# mowgli.net
KiCad netlist of a schematic drawn in EAGLE
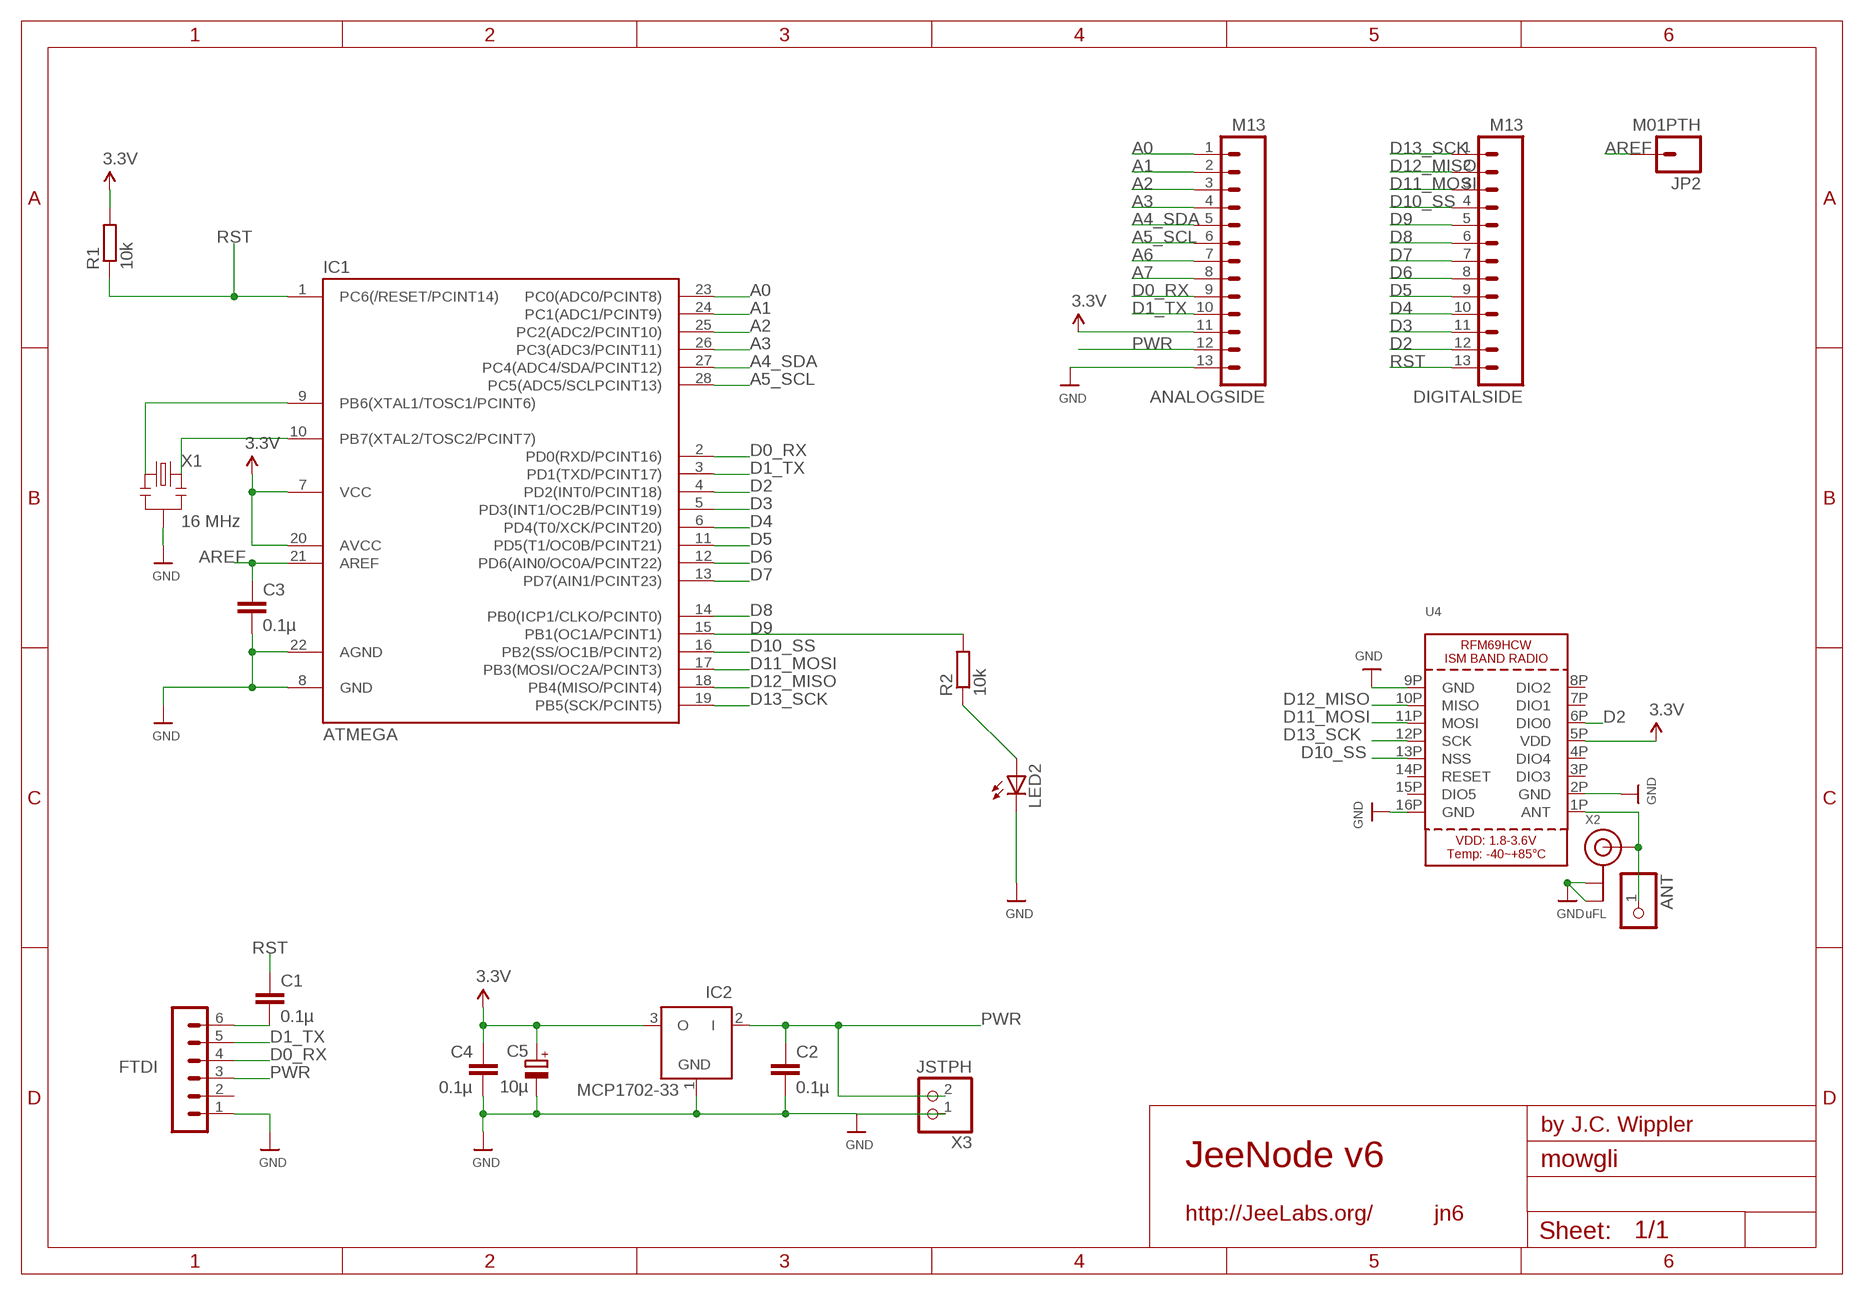
[diagram p0: schematic, sheet 1]

(export (version "E")
  (design (tool "Eeschema 10.0.6"))
  (components
    (comp (ref "ANALOGSIDE")
      (value "M13")
      (footprint "eagle-import:1X13")
      (libsource (lib "eagle-import") (part "M13"))
    )
    (comp (ref "ANT")
      (value "HEADER-1X1ROUND")
      (footprint "eagle-import:1X01_ROUND")
      (libsource (lib "eagle-import") (part "HEADER-1X1ROUND"))
    )
    (comp (ref "C1")
      (value "0.1µ")
      (footprint "eagle-import:C025-024X044")
      (libsource (lib "eagle-import") (part "C-EU025-024X044"))
    )
    (comp (ref "C2")
      (value "0.1µ")
      (footprint "eagle-import:C025-024X044")
      (libsource (lib "eagle-import") (part "C-EU025-024X044"))
    )
    (comp (ref "C3")
      (value "0.1µ")
      (footprint "eagle-import:C025-024X044")
      (libsource (lib "eagle-import") (part "C-EU025-024X044"))
    )
    (comp (ref "C4")
      (value "0.1µ")
      (footprint "eagle-import:C025-024X044")
      (libsource (lib "eagle-import") (part "C-EU025-024X044"))
    )
    (comp (ref "C5")
      (value "10µ")
      (footprint "eagle-import:E1,8-4")
      (libsource (lib "eagle-import") (part "CPOL-EUE1.8-4"))
    )
    (comp (ref "DIGITALSIDE")
      (value "M13")
      (footprint "eagle-import:1X13")
      (libsource (lib "eagle-import") (part "M13"))
    )
    (comp (ref "FTDI")
      (value "FTDI")
      (footprint "eagle-import:MA06-1")
      (libsource (lib "eagle-import") (part "MA06-1"))
    )
    (comp (ref "IC1")
      (value "ATMEGA")
      (footprint "eagle-import:DIL28-3")
      (libsource (lib "eagle-import") (part "ATMEGA48/88/168-PU"))
    )
    (comp (ref "IC2")
      (value "MCP1702-33")
      (footprint "eagle-import:TO92")
      (libsource (lib "eagle-import") (part "MCP1702Z"))
    )
    (comp (ref "JP2")
      (value "M01PTH")
      (footprint "eagle-import:1X01")
      (libsource (lib "eagle-import") (part "M01PTH"))
    )
    (comp (ref "LED2")
      (value "LED3MM")
      (footprint "eagle-import:LED3MM")
      (libsource (lib "eagle-import") (part "LED3MM"))
    )
    (comp (ref "R1")
      (value "10k")
      (footprint "eagle-import:0204_7")
      (libsource (lib "eagle-import") (part "R-EU_0204/7"))
    )
    (comp (ref "R2")
      (value "10k")
      (footprint "eagle-import:0204_7")
      (libsource (lib "eagle-import") (part "R-EU_0204/7"))
    )
    (comp (ref "U4")
      (value "RFM69HCW_SMT")
      (footprint "eagle-import:RFMHCW_SMT")
      (libsource (lib "eagle-import") (part "RFM69HCW_SMT"))
    )
    (comp (ref "X1")
      (value "16 MHz")
      (footprint "eagle-import:RESONATOR-PTH")
      (libsource (lib "eagle-import") (part "RESONATORPTH"))
    )
    (comp (ref "X2")
      (value "uFL")
      (footprint "eagle-import:U.FL")
      (libsource (lib "eagle-import") (part "ANTENNA_U.FL"))
    )
    (comp (ref "X3")
      (value "JSTPH")
      (footprint "eagle-import:JSTPH2")
      (libsource (lib "eagle-import") (part "CON_JST_PH_2PIN"))
    )
  )
  (nets
    (net (code "1") (name "/A0") (class "Default")
      (node (ref "ANALOGSIDE") (pin "1") (pinfunction "1_1") (pintype "passive"))
      (node (ref "IC1") (pin "23") (pinfunction "PC0(ADC0/PCINT8)_23") (pintype "bidirectional"))
    )
    (net (code "2") (name "/A1") (class "Default")
      (node (ref "ANALOGSIDE") (pin "2") (pinfunction "2_2") (pintype "passive"))
      (node (ref "IC1") (pin "24") (pinfunction "PC1(ADC1/PCINT9)_24") (pintype "bidirectional"))
    )
    (net (code "3") (name "/A2") (class "Default")
      (node (ref "ANALOGSIDE") (pin "3") (pinfunction "3_3") (pintype "passive"))
      (node (ref "IC1") (pin "25") (pinfunction "PC2(ADC2/PCINT10)_25") (pintype "bidirectional"))
    )
    (net (code "4") (name "/A3") (class "Default")
      (node (ref "ANALOGSIDE") (pin "4") (pinfunction "4_4") (pintype "passive"))
      (node (ref "IC1") (pin "26") (pinfunction "PC3(ADC3/PCINT11)_26") (pintype "bidirectional"))
    )
    (net (code "5") (name "/A4_SDA") (class "Default")
      (node (ref "ANALOGSIDE") (pin "5") (pinfunction "5_5") (pintype "passive"))
      (node (ref "IC1") (pin "27") (pinfunction "PC4(ADC4/SDA/PCINT12)_27") (pintype "bidirectional"))
    )
    (net (code "6") (name "/A5_SCL") (class "Default")
      (node (ref "ANALOGSIDE") (pin "6") (pinfunction "6_6") (pintype "passive"))
      (node (ref "IC1") (pin "28") (pinfunction "PC5(ADC5/SCLPCINT13)_28") (pintype "bidirectional"))
    )
    (net (code "7") (name "/A6") (class "Default")
      (node (ref "ANALOGSIDE") (pin "7") (pinfunction "7_7") (pintype "passive"))
    )
    (net (code "8") (name "/A7") (class "Default")
      (node (ref "ANALOGSIDE") (pin "8") (pinfunction "8_8") (pintype "passive"))
    )
    (net (code "9") (name "/AREF") (class "Default")
      (node (ref "C3") (pin "1") (pinfunction "1_1") (pintype "passive"))
      (node (ref "IC1") (pin "21") (pinfunction "AREF_21") (pintype "passive"))
      (node (ref "JP2") (pin "1") (pinfunction "1_1") (pintype "passive"))
    )
    (net (code "10") (name "/D0_RX") (class "Default")
      (node (ref "ANALOGSIDE") (pin "9") (pinfunction "9_9") (pintype "passive"))
      (node (ref "FTDI") (pin "4") (pinfunction "4_4") (pintype "passive"))
      (node (ref "IC1") (pin "2") (pinfunction "PD0(RXD/PCINT16)_2") (pintype "bidirectional"))
    )
    (net (code "11") (name "/D1_TX") (class "Default")
      (node (ref "ANALOGSIDE") (pin "10") (pinfunction "10_10") (pintype "passive"))
      (node (ref "FTDI") (pin "5") (pinfunction "5_5") (pintype "passive"))
      (node (ref "IC1") (pin "3") (pinfunction "PD1(TXD/PCINT17)_3") (pintype "bidirectional"))
    )
    (net (code "12") (name "/D2") (class "Default")
      (node (ref "DIGITALSIDE") (pin "12") (pinfunction "12_12") (pintype "passive"))
      (node (ref "IC1") (pin "4") (pinfunction "PD2(INT0/PCINT18)_4") (pintype "bidirectional"))
      (node (ref "U4") (pin "6P") (pinfunction "DIO0_6P") (pintype "bidirectional"))
    )
    (net (code "13") (name "/D3") (class "Default")
      (node (ref "DIGITALSIDE") (pin "11") (pinfunction "11_11") (pintype "passive"))
      (node (ref "IC1") (pin "5") (pinfunction "PD3(INT1/OC2B/PCINT19)_5") (pintype "bidirectional"))
    )
    (net (code "14") (name "/D4") (class "Default")
      (node (ref "DIGITALSIDE") (pin "10") (pinfunction "10_10") (pintype "passive"))
      (node (ref "IC1") (pin "6") (pinfunction "PD4(T0/XCK/PCINT20)_6") (pintype "bidirectional"))
    )
    (net (code "15") (name "/D5") (class "Default")
      (node (ref "DIGITALSIDE") (pin "9") (pinfunction "9_9") (pintype "passive"))
      (node (ref "IC1") (pin "11") (pinfunction "PD5(T1/OC0B/PCINT21)_11") (pintype "bidirectional"))
    )
    (net (code "16") (name "/D6") (class "Default")
      (node (ref "DIGITALSIDE") (pin "8") (pinfunction "8_8") (pintype "passive"))
      (node (ref "IC1") (pin "12") (pinfunction "PD6(AIN0/OC0A/PCINT22)_12") (pintype "bidirectional"))
    )
    (net (code "17") (name "/D7") (class "Default")
      (node (ref "DIGITALSIDE") (pin "7") (pinfunction "7_7") (pintype "passive"))
      (node (ref "IC1") (pin "13") (pinfunction "PD7(AIN1/PCINT23)_13") (pintype "bidirectional"))
    )
    (net (code "18") (name "/D8") (class "Default")
      (node (ref "DIGITALSIDE") (pin "6") (pinfunction "6_6") (pintype "passive"))
      (node (ref "IC1") (pin "14") (pinfunction "PB0(ICP1/CLKO/PCINT0)_14") (pintype "bidirectional"))
    )
    (net (code "19") (name "/D9") (class "Default")
      (node (ref "DIGITALSIDE") (pin "5") (pinfunction "5_5") (pintype "passive"))
      (node (ref "IC1") (pin "15") (pinfunction "PB1(OC1A/PCINT1)_15") (pintype "bidirectional"))
      (node (ref "R2") (pin "2") (pinfunction "2_2") (pintype "passive"))
    )
    (net (code "20") (name "/D10_SS") (class "Default")
      (node (ref "DIGITALSIDE") (pin "4") (pinfunction "4_4") (pintype "passive"))
      (node (ref "IC1") (pin "16") (pinfunction "PB2(SS/OC1B/PCINT2)_16") (pintype "bidirectional"))
      (node (ref "U4") (pin "13P") (pinfunction "NSS_13P") (pintype "input"))
    )
    (net (code "21") (name "/D11_MOSI") (class "Default")
      (node (ref "DIGITALSIDE") (pin "3") (pinfunction "3_3") (pintype "passive"))
      (node (ref "IC1") (pin "17") (pinfunction "PB3(MOSI/OC2A/PCINT3)_17") (pintype "bidirectional"))
      (node (ref "U4") (pin "11P") (pinfunction "MOSI_11P") (pintype "input"))
    )
    (net (code "22") (name "/D12_MISO") (class "Default")
      (node (ref "DIGITALSIDE") (pin "2") (pinfunction "2_2") (pintype "passive"))
      (node (ref "IC1") (pin "18") (pinfunction "PB4(MISO/PCINT4)_18") (pintype "bidirectional"))
      (node (ref "U4") (pin "10P") (pinfunction "MISO_10P") (pintype "output"))
    )
    (net (code "23") (name "/D13_SCK") (class "Default")
      (node (ref "DIGITALSIDE") (pin "1") (pinfunction "1_1") (pintype "passive"))
      (node (ref "IC1") (pin "19") (pinfunction "PB5(SCK/PCINT5)_19") (pintype "bidirectional"))
      (node (ref "U4") (pin "12P") (pinfunction "SCK_12P") (pintype "input"))
    )
    (net (code "24") (name "/PWR") (class "Default")
      (node (ref "ANALOGSIDE") (pin "12") (pinfunction "12_12") (pintype "passive"))
      (node (ref "C2") (pin "1") (pinfunction "1_1") (pintype "passive"))
      (node (ref "FTDI") (pin "3") (pinfunction "3_3") (pintype "passive"))
      (node (ref "IC2") (pin "2") (pinfunction "I_2") (pintype "input"))
      (node (ref "X3") (pin "2") (pinfunction "2_2") (pintype "passive"))
    )
    (net (code "25") (name "/RST") (class "Default")
      (node (ref "C1") (pin "1") (pinfunction "1_1") (pintype "passive"))
      (node (ref "DIGITALSIDE") (pin "13") (pinfunction "13_13") (pintype "passive"))
      (node (ref "IC1") (pin "1") (pinfunction "PC6(/RESET/PCINT14)_1") (pintype "bidirectional"))
      (node (ref "R1") (pin "1") (pinfunction "1_1") (pintype "passive"))
    )
    (net (code "26") (name "3.3V") (class "Default")
      (node (ref "ANALOGSIDE") (pin "11") (pinfunction "11_11") (pintype "passive"))
      (node (ref "C4") (pin "1") (pinfunction "1_1") (pintype "passive"))
      (node (ref "C5") (pin "+") (pinfunction "+_+") (pintype "passive"))
      (node (ref "IC1") (pin "20") (pinfunction "AVCC_20") (pintype "passive"))
      (node (ref "IC1") (pin "7") (pinfunction "VCC_7") (pintype "power_in"))
      (node (ref "IC2") (pin "3") (pinfunction "O_3") (pintype "input"))
      (node (ref "R1") (pin "2") (pinfunction "2_2") (pintype "passive"))
      (node (ref "U4") (pin "5P") (pinfunction "VDD_5P") (pintype "power_in"))
    )
    (net (code "27") (name "GND") (class "Default")
      (node (ref "ANALOGSIDE") (pin "13") (pinfunction "13_13") (pintype "passive"))
      (node (ref "C2") (pin "2") (pinfunction "2_2") (pintype "passive"))
      (node (ref "C3") (pin "2") (pinfunction "2_2") (pintype "passive"))
      (node (ref "C4") (pin "2") (pinfunction "2_2") (pintype "passive"))
      (node (ref "C5") (pin "-") (pinfunction "-_-") (pintype "passive"))
      (node (ref "FTDI") (pin "1") (pinfunction "1_1") (pintype "passive"))
      (node (ref "IC1") (pin "22") (pinfunction "AGND_22") (pintype "power_in"))
      (node (ref "IC1") (pin "8") (pinfunction "GND_8") (pintype "power_in"))
      (node (ref "IC2") (pin "1") (pinfunction "GND_1") (pintype "power_in"))
      (node (ref "LED2") (pin "K") (pinfunction "C_K") (pintype "passive"))
      (node (ref "U4") (pin "16P") (pinfunction "GND_16P") (pintype "power_in"))
      (node (ref "U4") (pin "2P") (pinfunction "GND_2P") (pintype "power_in"))
      (node (ref "U4") (pin "9P") (pinfunction "GND_9P") (pintype "power_in"))
      (node (ref "X1") (pin "2") (pinfunction "2_2") (pintype "passive"))
      (node (ref "X2") (pin "1") (pinfunction "GND_1") (pintype "passive"))
      (node (ref "X2") (pin "2") (pinfunction "GND_2") (pintype "passive"))
      (node (ref "X3") (pin "1") (pinfunction "1_1") (pintype "passive"))
    )
    (net (code "28") (name "Net-(C1-Pad2)") (class "Default")
      (node (ref "C1") (pin "2") (pinfunction "2_2") (pintype "passive"))
      (node (ref "FTDI") (pin "6") (pinfunction "6_6") (pintype "passive"))
    )
    (net (code "29") (name "Net-(IC1-PB6(XTAL1{slash}TOSC1{slash}PCINT6))") (class "Default")
      (node (ref "IC1") (pin "9") (pinfunction "PB6(XTAL1/TOSC1/PCINT6)_9") (pintype "bidirectional"))
      (node (ref "X1") (pin "1") (pinfunction "1_1") (pintype "passive"))
    )
    (net (code "30") (name "Net-(IC1-PB7(XTAL2{slash}TOSC2{slash}PCINT7))") (class "Default")
      (node (ref "IC1") (pin "10") (pinfunction "PB7(XTAL2/TOSC2/PCINT7)_10") (pintype "bidirectional"))
      (node (ref "X1") (pin "3") (pinfunction "3_3") (pintype "passive"))
    )
    (net (code "31") (name "Net-(LED2-PadA)") (class "Default")
      (node (ref "LED2") (pin "A") (pinfunction "A_A") (pintype "passive"))
      (node (ref "R2") (pin "1") (pinfunction "1_1") (pintype "passive"))
    )
    (net (code "32") (name "Net-(U4-ANT)") (class "Default")
      (node (ref "ANT") (pin "1") (pinfunction "1_1") (pintype "passive"))
      (node (ref "U4") (pin "1P") (pinfunction "ANT_1P") (pintype "bidirectional"))
      (node (ref "X2") (pin "3") (pinfunction "SIGNAL_3") (pintype "passive"))
    )
    (net (code "33") (name "unconnected-(FTDI-Pad2)") (class "Default")
      (node (ref "FTDI") (pin "2") (pinfunction "2_2") (pintype "passive"))
    )
    (net (code "34") (name "unconnected-(U4-DIO1-Pad7P)") (class "Default")
      (node (ref "U4") (pin "7P") (pinfunction "DIO1_7P") (pintype "bidirectional"))
    )
    (net (code "35") (name "unconnected-(U4-DIO2-Pad8P)") (class "Default")
      (node (ref "U4") (pin "8P") (pinfunction "DIO2_8P") (pintype "bidirectional"))
    )
    (net (code "36") (name "unconnected-(U4-DIO3-Pad3P)") (class "Default")
      (node (ref "U4") (pin "3P") (pinfunction "DIO3_3P") (pintype "bidirectional"))
    )
    (net (code "37") (name "unconnected-(U4-DIO4-Pad4P)") (class "Default")
      (node (ref "U4") (pin "4P") (pinfunction "DIO4_4P") (pintype "bidirectional"))
    )
    (net (code "38") (name "unconnected-(U4-DIO5-Pad15P)") (class "Default")
      (node (ref "U4") (pin "15P") (pinfunction "DIO5_15P") (pintype "bidirectional"))
    )
    (net (code "39") (name "unconnected-(U4-RESET-Pad14P)") (class "Default")
      (node (ref "U4") (pin "14P") (pinfunction "RESET_14P") (pintype "input"))
    )
  )
)
